# emitter.net
KiCad netlist of a schematic drawn in EAGLE
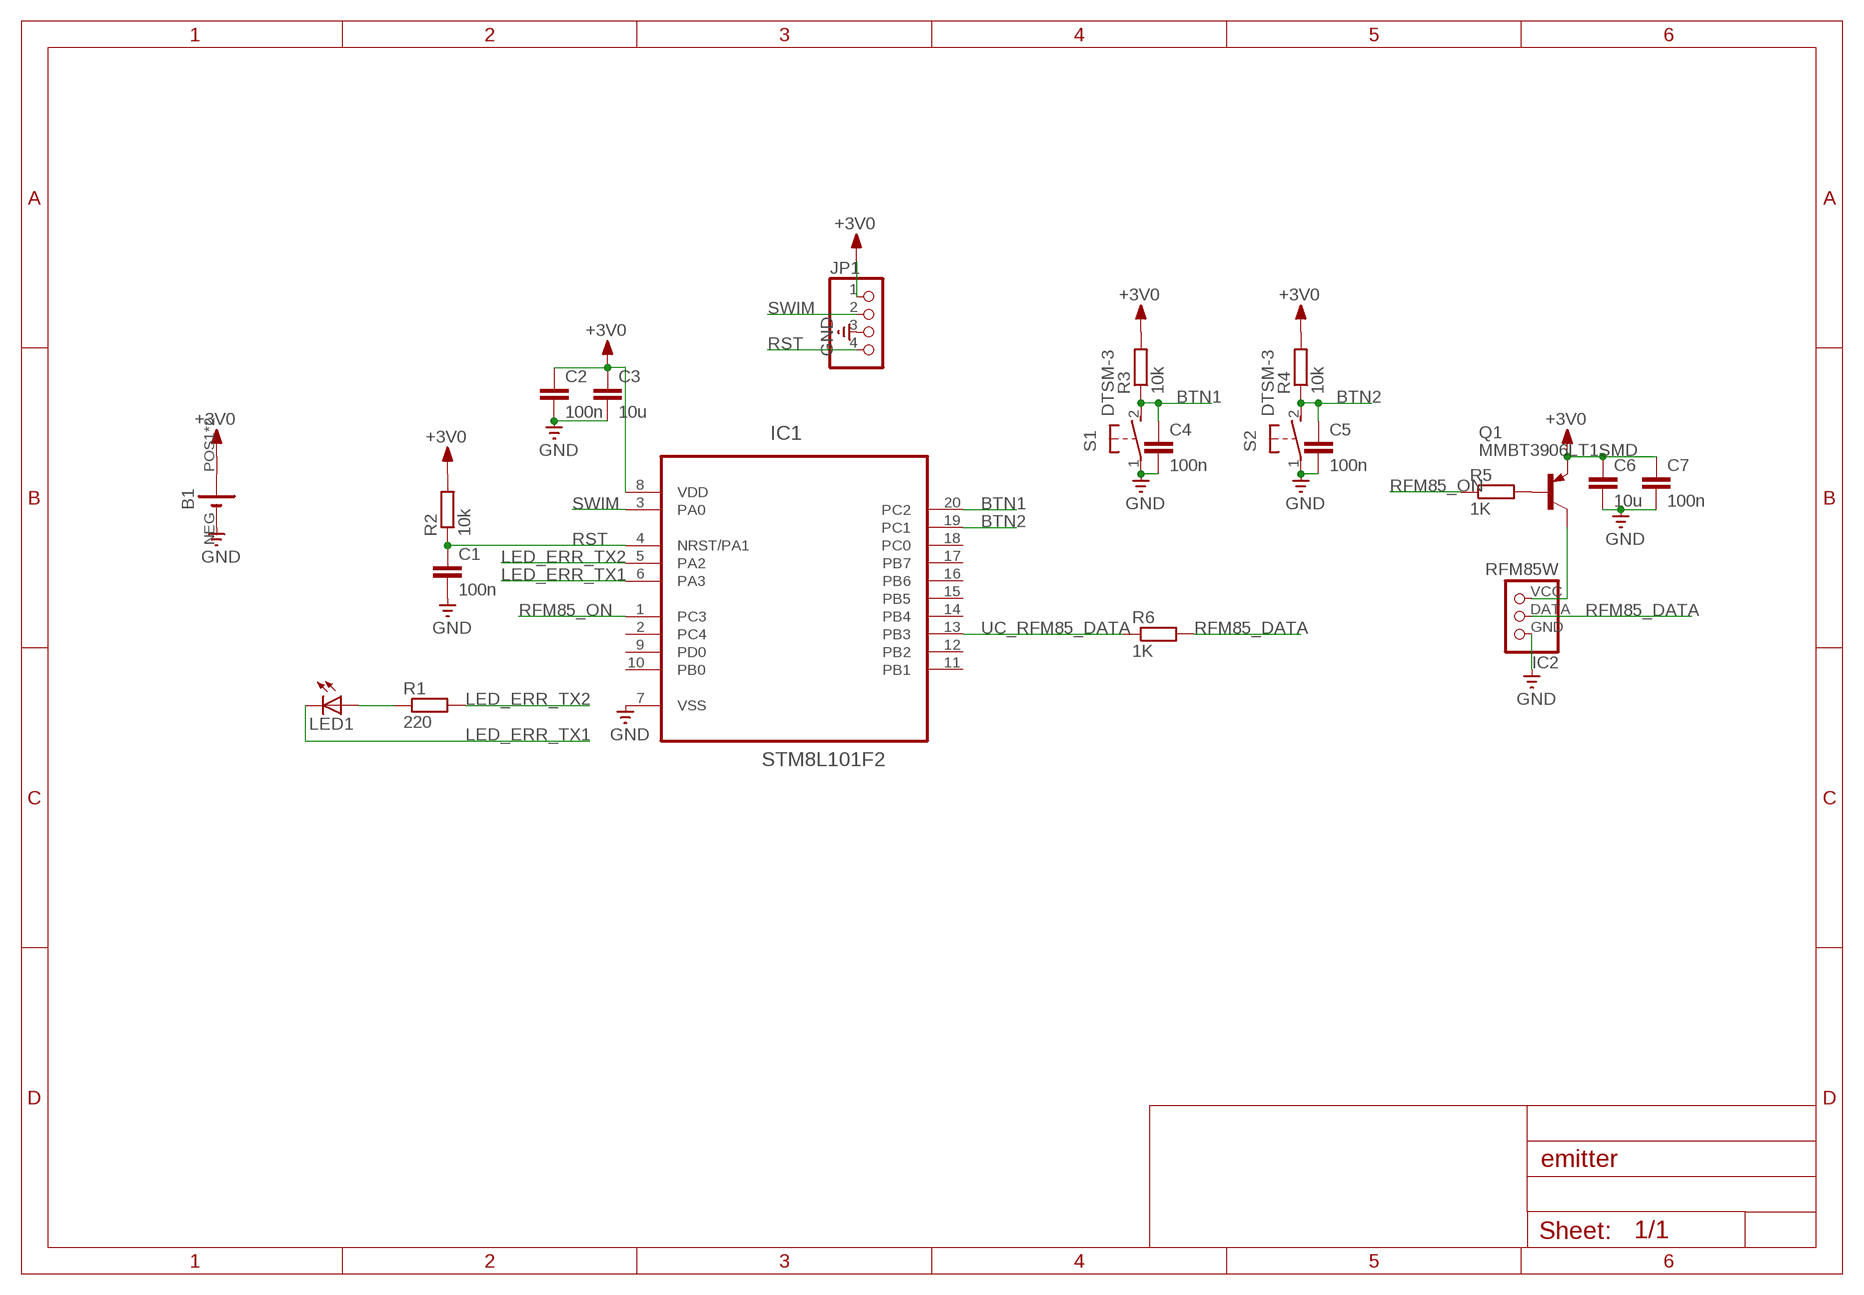
[diagram p0: schematic, sheet 1]

(export (version "E")
  (design (tool "Eeschema 10.0.6"))
  (components
    (comp (ref "B1")
      (value "CR2032_HOLDER_BC-2003")
      (footprint "eagle-import:CR2032_HOLDER_BC-2003")
      (libsource (lib "eagle-import") (part "CR2032_HOLDER_BC-2003"))
    )
    (comp (ref "C1")
      (value "100n")
      (footprint "eagle-import:C0603K")
      (libsource (lib "eagle-import") (part "C-EUC0603K"))
    )
    (comp (ref "C2")
      (value "100n")
      (footprint "eagle-import:C0603K")
      (libsource (lib "eagle-import") (part "C-EUC0603K"))
    )
    (comp (ref "C3")
      (value "10u")
      (footprint "eagle-import:C0805K")
      (libsource (lib "eagle-import") (part "C-EUC0805K"))
    )
    (comp (ref "C4")
      (value "100n")
      (footprint "eagle-import:C0603K")
      (libsource (lib "eagle-import") (part "C-EUC0603K"))
    )
    (comp (ref "C5")
      (value "100n")
      (footprint "eagle-import:C0603K")
      (libsource (lib "eagle-import") (part "C-EUC0603K"))
    )
    (comp (ref "C6")
      (value "10u")
      (footprint "eagle-import:C0805K")
      (libsource (lib "eagle-import") (part "C-EUC0805K"))
    )
    (comp (ref "C7")
      (value "100n")
      (footprint "eagle-import:C0603K")
      (libsource (lib "eagle-import") (part "C-EUC0603K"))
    )
    (comp (ref "IC1")
      (value "STM8L101F2")
      (footprint "eagle-import:TSSOP20")
      (libsource (lib "eagle-import") (part "STM8L101F2"))
    )
    (comp (ref "IC2")
      (value "RFM85W")
      (footprint "eagle-import:RFM85W_CON")
      (libsource (lib "eagle-import") (part "RFM85W"))
    )
    (comp (ref "JP1")
      (value "PINHD-1X4")
      (footprint "eagle-import:1X04")
      (libsource (lib "eagle-import") (part "PINHD-1X4"))
    )
    (comp (ref "LED1")
      (value "LED3MM")
      (footprint "eagle-import:LED3MM")
      (libsource (lib "eagle-import") (part "LED3MM"))
    )
    (comp (ref "Q1")
      (value "MMBT3906LT1SMD")
      (footprint "eagle-import:SOT23-BEC")
      (libsource (lib "eagle-import") (part "MMBT3906SMDLT1"))
    )
    (comp (ref "R1")
      (value "220")
      (footprint "eagle-import:R0603")
      (libsource (lib "eagle-import") (part "R-EU_R0603"))
    )
    (comp (ref "R2")
      (value "10k")
      (footprint "eagle-import:R0603")
      (libsource (lib "eagle-import") (part "R-EU_R0603"))
    )
    (comp (ref "R3")
      (value "10k")
      (footprint "eagle-import:R0603")
      (libsource (lib "eagle-import") (part "R-EU_R0603"))
    )
    (comp (ref "R4")
      (value "10k")
      (footprint "eagle-import:R0603")
      (libsource (lib "eagle-import") (part "R-EU_R0603"))
    )
    (comp (ref "R5")
      (value "1K")
      (footprint "eagle-import:R0603")
      (libsource (lib "eagle-import") (part "R-EU_R0603"))
    )
    (comp (ref "R6")
      (value "1K")
      (footprint "eagle-import:R0603")
      (libsource (lib "eagle-import") (part "R-EU_R0603"))
    )
    (comp (ref "S1")
      (value "DTSM-3")
      (footprint "eagle-import:DTSM-3")
      (libsource (lib "eagle-import") (part "DTSM-3"))
    )
    (comp (ref "S2")
      (value "DTSM-3")
      (footprint "eagle-import:DTSM-3")
      (libsource (lib "eagle-import") (part "DTSM-3"))
    )
  )
  (nets
    (net (code "1") (name "+3V0") (class "Default")
      (node (ref "B1") (pin "POS1") (pinfunction "+_POS1") (pintype "passive"))
      (node (ref "B1") (pin "POS2") (pinfunction "+_POS2") (pintype "passive"))
      (node (ref "C2") (pin "1") (pinfunction "1_1") (pintype "passive"))
      (node (ref "C3") (pin "1") (pinfunction "1_1") (pintype "passive"))
      (node (ref "C6") (pin "1") (pinfunction "1_1") (pintype "passive"))
      (node (ref "C7") (pin "1") (pinfunction "1_1") (pintype "passive"))
      (node (ref "IC1") (pin "8") (pinfunction "VDD_8") (pintype "power_in"))
      (node (ref "JP1") (pin "1") (pinfunction "1_1") (pintype "passive"))
      (node (ref "Q1") (pin "E") (pinfunction "E_E") (pintype "passive"))
      (node (ref "R2") (pin "2") (pinfunction "2_2") (pintype "passive"))
      (node (ref "R3") (pin "2") (pinfunction "2_2") (pintype "passive"))
      (node (ref "R4") (pin "2") (pinfunction "2_2") (pintype "passive"))
    )
    (net (code "2") (name "/BTN1") (class "Default")
      (node (ref "C4") (pin "1") (pinfunction "1_1") (pintype "passive"))
      (node (ref "IC1") (pin "20") (pinfunction "PC2_20") (pintype "bidirectional"))
      (node (ref "R3") (pin "1") (pinfunction "1_1") (pintype "passive"))
      (node (ref "S1") (pin "2") (pinfunction "2_2") (pintype "passive"))
    )
    (net (code "3") (name "/BTN2") (class "Default")
      (node (ref "C5") (pin "1") (pinfunction "1_1") (pintype "passive"))
      (node (ref "IC1") (pin "19") (pinfunction "PC1_19") (pintype "bidirectional"))
      (node (ref "R4") (pin "1") (pinfunction "1_1") (pintype "passive"))
      (node (ref "S2") (pin "2") (pinfunction "2_2") (pintype "passive"))
    )
    (net (code "4") (name "/LED_ERR_TX1") (class "Default")
      (node (ref "IC1") (pin "6") (pinfunction "PA3_6") (pintype "bidirectional"))
      (node (ref "LED1") (pin "K") (pinfunction "C_K") (pintype "passive"))
    )
    (net (code "5") (name "/LED_ERR_TX2") (class "Default")
      (node (ref "IC1") (pin "5") (pinfunction "PA2_5") (pintype "bidirectional"))
      (node (ref "R1") (pin "2") (pinfunction "2_2") (pintype "passive"))
    )
    (net (code "6") (name "/RFM85_DATA") (class "Default")
      (node (ref "IC2") (pin "DATA") (pinfunction "2_DATA") (pintype "passive"))
      (node (ref "R6") (pin "2") (pinfunction "2_2") (pintype "passive"))
    )
    (net (code "7") (name "/RFM85_ON") (class "Default")
      (node (ref "IC1") (pin "1") (pinfunction "PC3_1") (pintype "bidirectional"))
      (node (ref "R5") (pin "1") (pinfunction "1_1") (pintype "passive"))
    )
    (net (code "8") (name "/RST") (class "Default")
      (node (ref "C1") (pin "1") (pinfunction "1_1") (pintype "passive"))
      (node (ref "IC1") (pin "4") (pinfunction "NRST/PA1_4") (pintype "bidirectional"))
      (node (ref "JP1") (pin "4") (pinfunction "4_4") (pintype "passive"))
      (node (ref "R2") (pin "1") (pinfunction "1_1") (pintype "passive"))
    )
    (net (code "9") (name "/SWIM") (class "Default")
      (node (ref "IC1") (pin "3") (pinfunction "PA0_3") (pintype "power_in"))
      (node (ref "JP1") (pin "2") (pinfunction "2_2") (pintype "passive"))
    )
    (net (code "10") (name "/UC_RFM85_DATA") (class "Default")
      (node (ref "IC1") (pin "13") (pinfunction "PB3_13") (pintype "bidirectional"))
      (node (ref "R6") (pin "1") (pinfunction "1_1") (pintype "passive"))
    )
    (net (code "11") (name "GND") (class "Default")
      (node (ref "B1") (pin "NEG") (pinfunction "-_NEG") (pintype "passive"))
      (node (ref "C1") (pin "2") (pinfunction "2_2") (pintype "passive"))
      (node (ref "C2") (pin "2") (pinfunction "2_2") (pintype "passive"))
      (node (ref "C3") (pin "2") (pinfunction "2_2") (pintype "passive"))
      (node (ref "C4") (pin "2") (pinfunction "2_2") (pintype "passive"))
      (node (ref "C5") (pin "2") (pinfunction "2_2") (pintype "passive"))
      (node (ref "C6") (pin "2") (pinfunction "2_2") (pintype "passive"))
      (node (ref "C7") (pin "2") (pinfunction "2_2") (pintype "passive"))
      (node (ref "IC1") (pin "7") (pinfunction "VSS_7") (pintype "power_in"))
      (node (ref "IC2") (pin "GND") (pinfunction "1_GND") (pintype "passive"))
      (node (ref "JP1") (pin "3") (pinfunction "3_3") (pintype "passive"))
      (node (ref "S1") (pin "1") (pinfunction "1_1") (pintype "passive"))
      (node (ref "S2") (pin "1") (pinfunction "1_1") (pintype "passive"))
    )
    (net (code "12") (name "Net-(IC2-3)") (class "Default")
      (node (ref "IC2") (pin "VCC") (pinfunction "3_VCC") (pintype "passive"))
      (node (ref "Q1") (pin "C") (pinfunction "C_C") (pintype "passive"))
    )
    (net (code "13") (name "Net-(LED1-PadA)") (class "Default")
      (node (ref "LED1") (pin "A") (pinfunction "A_A") (pintype "passive"))
      (node (ref "R1") (pin "1") (pinfunction "1_1") (pintype "passive"))
    )
    (net (code "14") (name "Net-(Q1-PadB)") (class "Default")
      (node (ref "Q1") (pin "B") (pinfunction "B_B") (pintype "passive"))
      (node (ref "R5") (pin "2") (pinfunction "2_2") (pintype "passive"))
    )
    (net (code "15") (name "unconnected-(IC1-PB0-Pad10)") (class "Default")
      (node (ref "IC1") (pin "10") (pinfunction "PB0_10") (pintype "bidirectional"))
    )
    (net (code "16") (name "unconnected-(IC1-PB1-Pad11)") (class "Default")
      (node (ref "IC1") (pin "11") (pinfunction "PB1_11") (pintype "bidirectional"))
    )
    (net (code "17") (name "unconnected-(IC1-PB2-Pad12)") (class "Default")
      (node (ref "IC1") (pin "12") (pinfunction "PB2_12") (pintype "bidirectional"))
    )
    (net (code "18") (name "unconnected-(IC1-PB4-Pad14)") (class "Default")
      (node (ref "IC1") (pin "14") (pinfunction "PB4_14") (pintype "bidirectional"))
    )
    (net (code "19") (name "unconnected-(IC1-PB5-Pad15)") (class "Default")
      (node (ref "IC1") (pin "15") (pinfunction "PB5_15") (pintype "bidirectional"))
    )
    (net (code "20") (name "unconnected-(IC1-PB6-Pad16)") (class "Default")
      (node (ref "IC1") (pin "16") (pinfunction "PB6_16") (pintype "bidirectional"))
    )
    (net (code "21") (name "unconnected-(IC1-PB7-Pad17)") (class "Default")
      (node (ref "IC1") (pin "17") (pinfunction "PB7_17") (pintype "bidirectional"))
    )
    (net (code "22") (name "unconnected-(IC1-PC0-Pad18)") (class "Default")
      (node (ref "IC1") (pin "18") (pinfunction "PC0_18") (pintype "bidirectional"))
    )
    (net (code "23") (name "unconnected-(IC1-PC4-Pad2)") (class "Default")
      (node (ref "IC1") (pin "2") (pinfunction "PC4_2") (pintype "bidirectional"))
    )
    (net (code "24") (name "unconnected-(IC1-PD0-Pad9)") (class "Default")
      (node (ref "IC1") (pin "9") (pinfunction "PD0_9") (pintype "bidirectional"))
    )
  )
)
